# FT2232H.net
KiCad netlist of a schematic drawn in Altium Designer
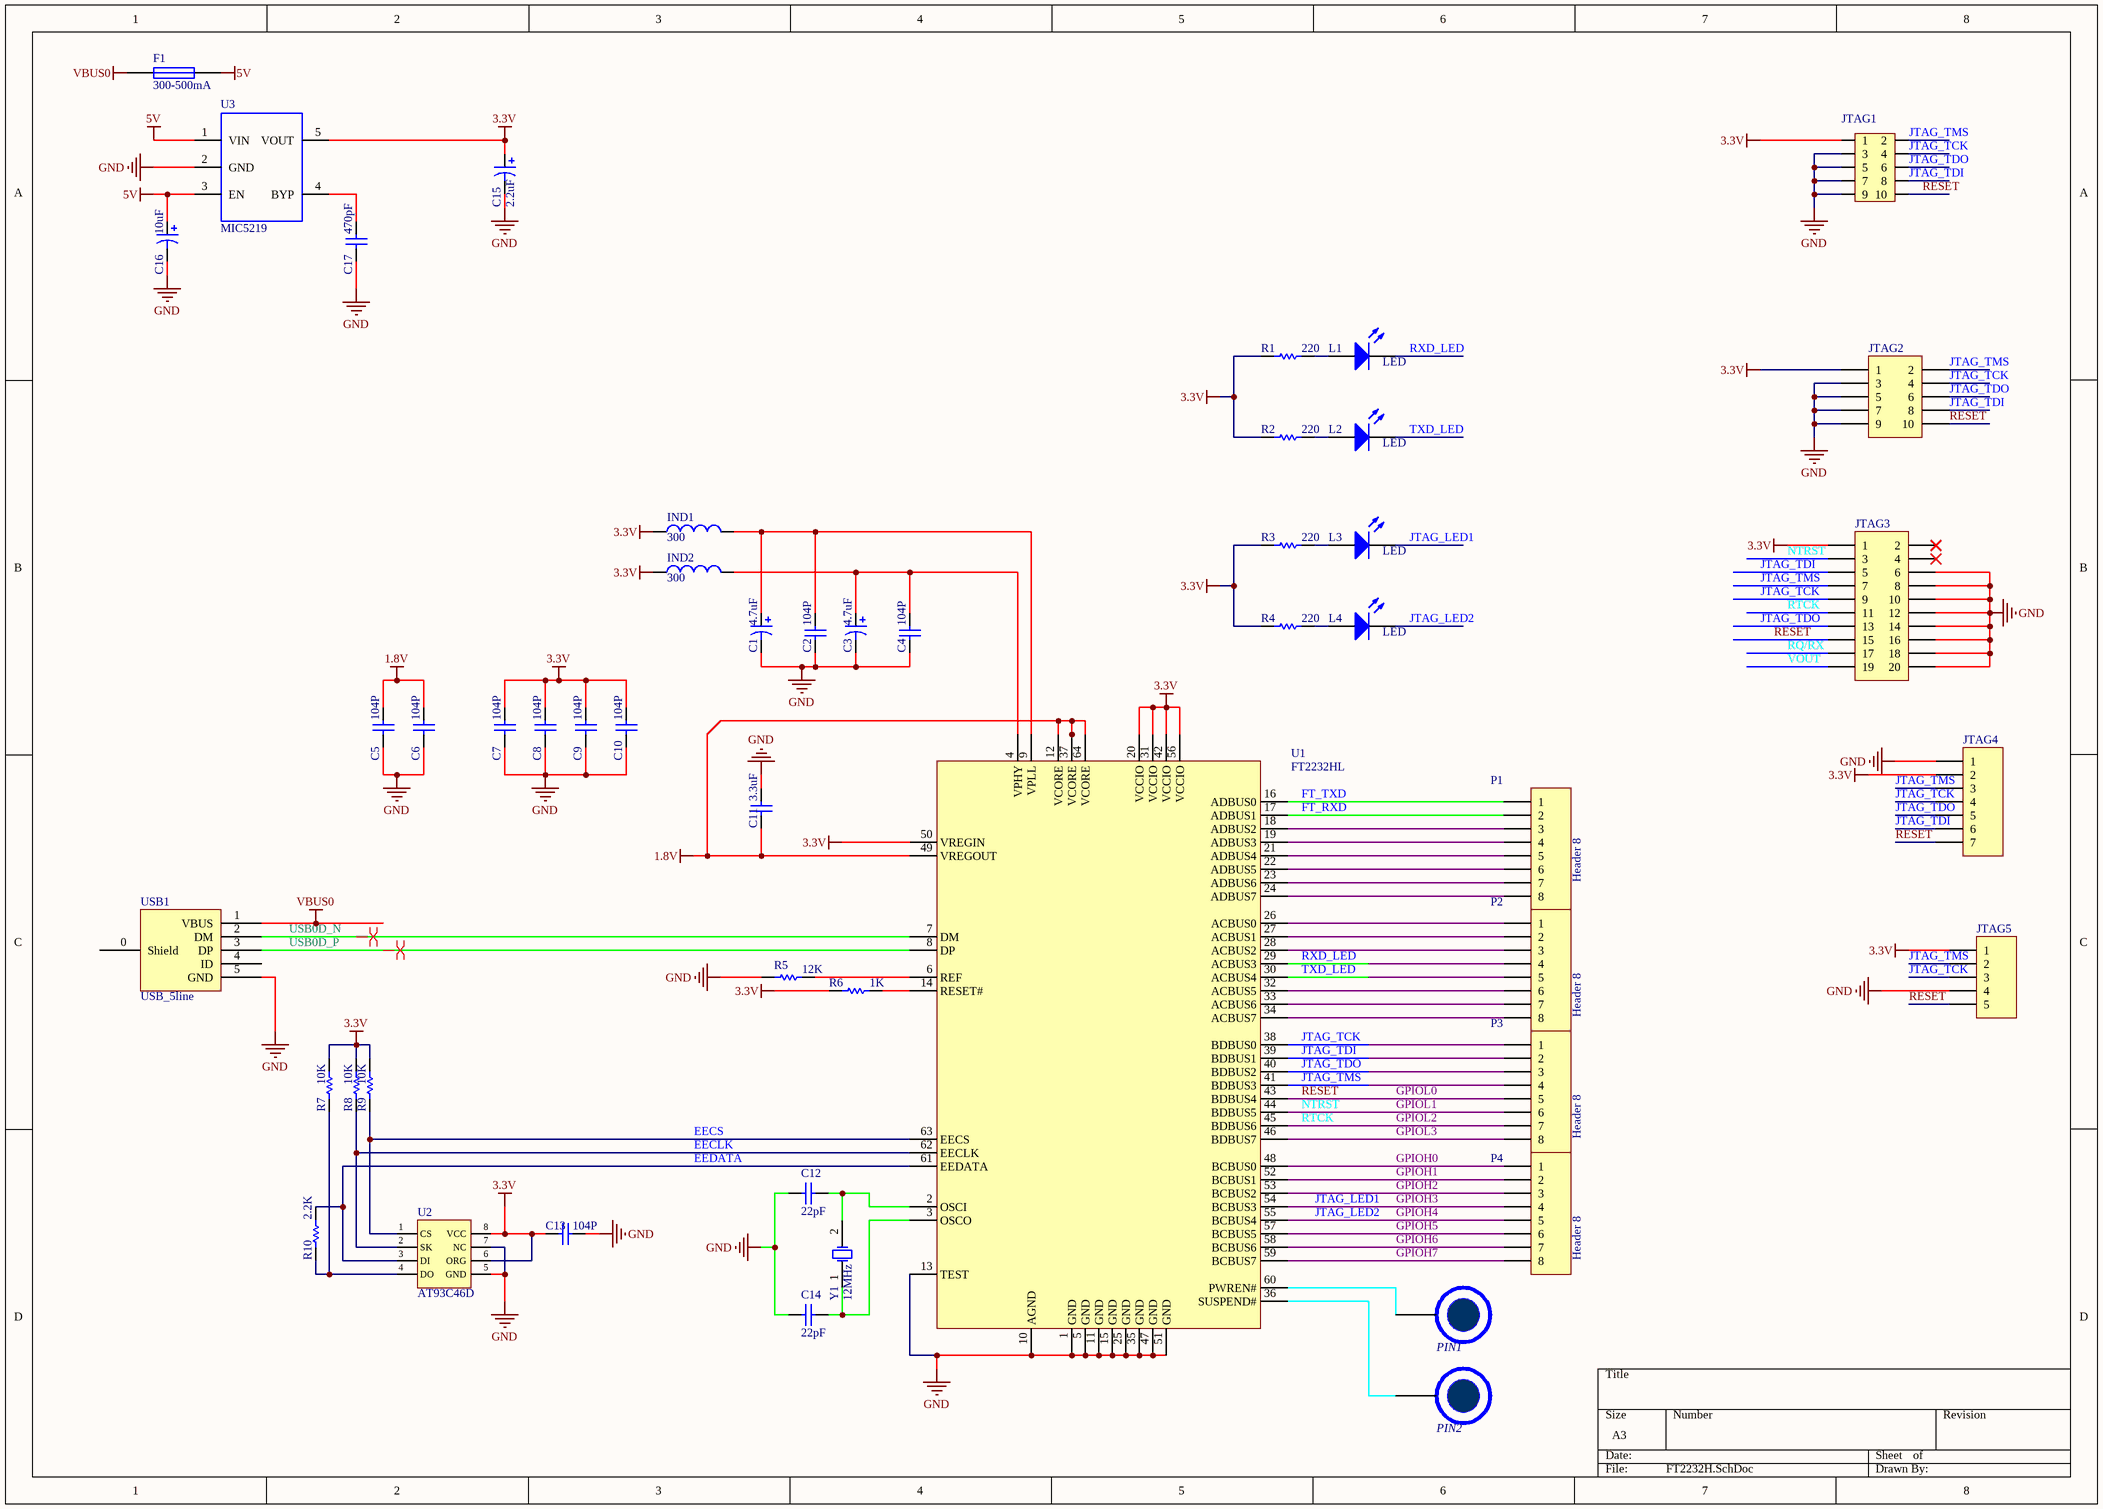
[diagram p0: FT2232H.SchDoc]

(export (version "E")
  (design (tool "Eeschema 10.0.6"))
  (components
    (comp (ref "C1")
      (value "4.7uF")
      (footprint "1608[0603]")
      (description "Polarized Capacitor (Radial)")
      (fields (field (name "Comment") "Cap Pol1") (field (name "PUBLISHER") "Altium Limited"))
      (libsource (lib "Miscellaneous Devices") (part "Cap Pol1"))
    )
    (comp (ref "C2")
      (value "104P")
      (footprint "1608[0603]")
      (description "贴片电容")
      (fields (field (name "Comment") "Cap") (field (name "PUBLISHER") "Altium Limited"))
      (libsource (lib "Sparks") (part "Cap"))
    )
    (comp (ref "C3")
      (value "4.7uF")
      (footprint "1608[0603]")
      (description "Polarized Capacitor (Radial)")
      (fields (field (name "Comment") "Cap Pol1") (field (name "PUBLISHER") "Altium Limited"))
      (libsource (lib "Miscellaneous Devices") (part "Cap Pol1"))
    )
    (comp (ref "C4")
      (value "104P")
      (footprint "1608[0603]")
      (description "贴片电容")
      (fields (field (name "Comment") "Cap") (field (name "PUBLISHER") "Altium Limited"))
      (libsource (lib "Sparks") (part "Cap"))
    )
    (comp (ref "C5")
      (value "104P")
      (footprint "1608[0603]")
      (description "贴片电容")
      (fields (field (name "Comment") "Cap") (field (name "PUBLISHER") "Altium Limited"))
      (libsource (lib "Sparks") (part "Cap"))
    )
    (comp (ref "C6")
      (value "104P")
      (footprint "1608[0603]")
      (description "贴片电容")
      (fields (field (name "Comment") "Cap") (field (name "PUBLISHER") "Altium Limited"))
      (libsource (lib "Sparks") (part "Cap"))
    )
    (comp (ref "C7")
      (value "104P")
      (footprint "1608[0603]")
      (description "贴片电容")
      (fields (field (name "Comment") "Cap") (field (name "PUBLISHER") "Altium Limited"))
      (libsource (lib "Sparks") (part "Cap"))
    )
    (comp (ref "C8")
      (value "104P")
      (footprint "1608[0603]")
      (description "贴片电容")
      (fields (field (name "Comment") "Cap") (field (name "PUBLISHER") "Altium Limited"))
      (libsource (lib "Sparks") (part "Cap"))
    )
    (comp (ref "C9")
      (value "104P")
      (footprint "1608[0603]")
      (description "贴片电容")
      (fields (field (name "Comment") "Cap") (field (name "PUBLISHER") "Altium Limited"))
      (libsource (lib "Sparks") (part "Cap"))
    )
    (comp (ref "C10")
      (value "104P")
      (footprint "1608[0603]")
      (description "贴片电容")
      (fields (field (name "Comment") "Cap") (field (name "PUBLISHER") "Altium Limited"))
      (libsource (lib "Sparks") (part "Cap"))
    )
    (comp (ref "C11")
      (value "3.3uF")
      (footprint "1608[0603]")
      (description "贴片电容")
      (fields (field (name "Comment") "Cap") (field (name "PUBLISHER") "Altium Limited"))
      (libsource (lib "Sparks") (part "Cap"))
    )
    (comp (ref "C12")
      (value "22pF")
      (footprint "1608[0603]")
      (description "贴片电容")
      (fields (field (name "Comment") "Cap") (field (name "PUBLISHER") "Altium Limited"))
      (libsource (lib "Sparks") (part "Cap"))
    )
    (comp (ref "C13")
      (value "104P")
      (footprint "1608[0603]")
      (description "贴片电容")
      (fields (field (name "Comment") "Cap") (field (name "PUBLISHER") "Altium Limited"))
      (libsource (lib "Sparks") (part "Cap"))
    )
    (comp (ref "C14")
      (value "22pF")
      (footprint "1608[0603]")
      (description "贴片电容")
      (fields (field (name "Comment") "Cap") (field (name "PUBLISHER") "Altium Limited"))
      (libsource (lib "Sparks") (part "Cap"))
    )
    (comp (ref "C15")
      (value "2.2uF")
      (footprint "1206(2)")
      (description "Polarized Capacitor (Radial)")
      (fields (field (name "Comment") "Cap Pol1") (field (name "PUBLISHER") "Altium Limited"))
      (libsource (lib "Miscellaneous Devices") (part "Cap Pol1"))
    )
    (comp (ref "C16")
      (value "10uF")
      (footprint "1206(2)")
      (description "Polarized Capacitor (Radial)")
      (fields (field (name "Comment") "Cap Pol1") (field (name "PUBLISHER") "Altium Limited"))
      (libsource (lib "Miscellaneous Devices") (part "Cap Pol1"))
    )
    (comp (ref "C17")
      (value "470pF")
      (footprint "1608[0603]")
      (description "贴片电容")
      (fields (field (name "Comment") "Cap") (field (name "PUBLISHER") "Altium Limited"))
      (libsource (lib "Sparks") (part "Cap"))
    )
    (comp (ref "F1")
      (value "300-500mA")
      (footprint "1206(2)")
      (description "Fuse")
      (fields (field (name "PUBLISHER") "Altium Limited"))
      (libsource (lib "K60-V4.0") (part "Fuse 1"))
    )
    (comp (ref "IND1")
      (value "300")
      (footprint "1608[0603]")
      (description "Inductor")
      (fields (field (name "PUBLISHER") "Altium Limited"))
      (libsource (lib "Miscellaneous Devices") (part "Inductor"))
    )
    (comp (ref "IND2")
      (value "300")
      (footprint "1608[0603]")
      (description "Inductor")
      (fields (field (name "PUBLISHER") "Altium Limited"))
      (libsource (lib "Miscellaneous Devices") (part "Inductor"))
    )
    (comp (ref "JTAG1")
      (value "Header 5X2")
      (footprint "IDC5X2")
      (description "Header, 5-Pin, Dual row")
      (libsource (lib "K60-V4.0") (part "Header 5X2"))
    )
    (comp (ref "JTAG2")
      (value "MHDR2X5")
      (footprint "MHDR2X5")
      (description "Header, 5-Pin, Dual row")
      (fields (field (name "PUBLISHER") "Altium Limited"))
      (libsource (lib "Miscellaneous Connectors") (part "MHDR2X5"))
    )
    (comp (ref "JTAG3")
      (value "Header 10X2")
      (footprint "HDR2X10")
      (description "Header, 10-Pin, Dual row")
      (fields (field (name "PUBLISHER") "Altium Limited"))
      (libsource (lib "Sparks") (part "Header 10X2"))
    )
    (comp (ref "JTAG4")
      (value "MHDR1X7")
      (footprint "MHDR1X7")
      (description "Header, 7-Pin")
      (fields (field (name "PUBLISHER") "Altium Limited"))
      (libsource (lib "Miscellaneous Connectors") (part "MHDR1X7"))
    )
    (comp (ref "JTAG5")
      (value "Header 5")
      (footprint "HDR1X5")
      (description "Header, 5-Pin")
      (fields (field (name "PUBLISHER") "Altium Limited"))
      (libsource (lib "Miscellaneous Connectors") (part "Header 5"))
    )
    (comp (ref "L1") (value "LED") (footprint "1608[0603]") (libsource (lib "Sparks") (part "LED")))
    (comp (ref "L2") (value "LED") (footprint "1608[0603]") (libsource (lib "Sparks") (part "LED")))
    (comp (ref "L3") (value "LED") (footprint "1608[0603]") (libsource (lib "Sparks") (part "LED")))
    (comp (ref "L4") (value "LED") (footprint "1608[0603]") (libsource (lib "Sparks") (part "LED")))
    (comp (ref "P1")
      (value "Header 8")
      (footprint "HDR1X8")
      (description "Header, 8-Pin")
      (fields (field (name "PUBLISHER") "Altium Limited"))
      (libsource (lib "Sparks") (part "Header 8"))
    )
    (comp (ref "P2")
      (value "Header 8")
      (footprint "HDR1X8")
      (description "Header, 8-Pin")
      (fields (field (name "PUBLISHER") "Altium Limited"))
      (libsource (lib "Sparks") (part "Header 8"))
    )
    (comp (ref "P3")
      (value "Header 8")
      (footprint "HDR1X8")
      (description "Header, 8-Pin")
      (fields (field (name "PUBLISHER") "Altium Limited"))
      (libsource (lib "Sparks") (part "Header 8"))
    )
    (comp (ref "P4")
      (value "Header 8")
      (footprint "HDR1X8")
      (description "Header, 8-Pin")
      (fields (field (name "PUBLISHER") "Altium Limited"))
      (libsource (lib "Sparks") (part "Header 8"))
    )
    (comp (ref "PIN1") (value "PIN") (footprint "PIN") (libsource (lib "2号库") (part "PIN")))
    (comp (ref "PIN2") (value "PIN") (footprint "PIN") (libsource (lib "2号库") (part "PIN")))
    (comp (ref "R1")
      (value "220")
      (footprint "1608[0603]")
      (description "贴片电阻")
      (fields (field (name "Comment") "Res") (field (name "PUBLISHER") "Altium Limited"))
      (libsource (lib "Sparks") (part "Res"))
    )
    (comp (ref "R2")
      (value "220")
      (footprint "1608[0603]")
      (description "贴片电阻")
      (fields (field (name "Comment") "Res") (field (name "PUBLISHER") "Altium Limited"))
      (libsource (lib "Sparks") (part "Res"))
    )
    (comp (ref "R3")
      (value "220")
      (footprint "1608[0603]")
      (description "贴片电阻")
      (fields (field (name "Comment") "Res") (field (name "PUBLISHER") "Altium Limited"))
      (libsource (lib "Sparks") (part "Res"))
    )
    (comp (ref "R4")
      (value "220")
      (footprint "1608[0603]")
      (description "贴片电阻")
      (fields (field (name "Comment") "Res") (field (name "PUBLISHER") "Altium Limited"))
      (libsource (lib "Sparks") (part "Res"))
    )
    (comp (ref "R5")
      (value "12K")
      (footprint "1608[0603]")
      (description "贴片电阻")
      (fields (field (name "Comment") "Res") (field (name "PUBLISHER") "Altium Limited"))
      (libsource (lib "Sparks") (part "Res"))
    )
    (comp (ref "R6")
      (value "1K")
      (footprint "1608[0603]")
      (description "贴片电阻")
      (fields (field (name "Comment") "Res") (field (name "PUBLISHER") "Altium Limited"))
      (libsource (lib "Sparks") (part "Res"))
    )
    (comp (ref "R7")
      (value "10K")
      (footprint "1608[0603]")
      (description "贴片电阻")
      (fields (field (name "Comment") "Res") (field (name "PUBLISHER") "Altium Limited"))
      (libsource (lib "Sparks") (part "Res"))
    )
    (comp (ref "R8")
      (value "10K")
      (footprint "1608[0603]")
      (description "贴片电阻")
      (fields (field (name "Comment") "Res") (field (name "PUBLISHER") "Altium Limited"))
      (libsource (lib "Sparks") (part "Res"))
    )
    (comp (ref "R9")
      (value "10K")
      (footprint "1608[0603]")
      (description "贴片电阻")
      (fields (field (name "Comment") "Res") (field (name "PUBLISHER") "Altium Limited"))
      (libsource (lib "Sparks") (part "Res"))
    )
    (comp (ref "R10")
      (value "2.2K")
      (footprint "1608[0603]")
      (description "贴片电阻")
      (fields (field (name "Comment") "Res") (field (name "PUBLISHER") "Altium Limited"))
      (libsource (lib "Sparks") (part "Res"))
    )
    (comp (ref "U1") (value "FT2232HL") (footprint "LQFP-64") (libsource (lib "2号库") (part "FT2232HL")))
    (comp (ref "U2")
      (value "AT93C46D")
      (footprint "TSOP65P640X120-8N-AT93C46D")
      (libsource (lib "2号库") (part "AT93C46D"))
    )
    (comp (ref "U3")
      (value "MIC5219")
      (footprint "SOT-23-5")
      (description "LDO")
      (libsource (lib "K60-V4.0") (part "MIC5219"))
    )
    (comp (ref "USB1")
      (value "USB_5line")
      (footprint "USB-MICRO-5P-2F")
      (libsource (lib "2号库") (part "USB_5line"))
    )
    (comp (ref "Y1")
      (value "12MHz")
      (footprint "5032")
      (description "晶体振荡器")
      (fields (field (name "PUBLISHER") "Altium Limited"))
      (libsource (lib "Sparks") (part "XTAL"))
    )
  )
  (nets
    (net (code "1") (name "/EECLK") (class "Default")
      (node (ref "R8") (pin "2") (pinfunction "2_2") (pintype "passive"))
      (node (ref "U1") (pin "62") (pinfunction "EECLK_62") (pintype "passive"))
      (node (ref "U2") (pin "2") (pinfunction "SK_2") (pintype "passive"))
    )
    (net (code "2") (name "/EECS") (class "Default")
      (node (ref "R9") (pin "2") (pinfunction "2_2") (pintype "passive"))
      (node (ref "U1") (pin "63") (pinfunction "EECS_63") (pintype "passive"))
      (node (ref "U2") (pin "1") (pinfunction "CS_1") (pintype "passive"))
    )
    (net (code "3") (name "/EEDATA") (class "Default")
      (node (ref "R10") (pin "1") (pinfunction "1_1") (pintype "passive"))
      (node (ref "U1") (pin "61") (pinfunction "EEDATA_61") (pintype "passive"))
      (node (ref "U2") (pin "3") (pinfunction "DI_3") (pintype "passive"))
    )
    (net (code "4") (name "/FT_RXD") (class "Default")
      (node (ref "P1") (pin "2") (pinfunction "2_2") (pintype "passive"))
      (node (ref "U1") (pin "17") (pinfunction "ADBUS1_17") (pintype "passive"))
    )
    (net (code "5") (name "/FT_TXD") (class "Default")
      (node (ref "P1") (pin "1") (pinfunction "1_1") (pintype "passive"))
      (node (ref "U1") (pin "16") (pinfunction "ADBUS0_16") (pintype "passive"))
    )
    (net (code "6") (name "/GPIOH0") (class "Default")
      (node (ref "P4") (pin "1") (pinfunction "1_1") (pintype "passive"))
      (node (ref "U1") (pin "48") (pinfunction "BCBUS0_48") (pintype "passive"))
    )
    (net (code "7") (name "/GPIOH1") (class "Default")
      (node (ref "P4") (pin "2") (pinfunction "2_2") (pintype "passive"))
      (node (ref "U1") (pin "52") (pinfunction "BCBUS1_52") (pintype "passive"))
    )
    (net (code "8") (name "/GPIOH2") (class "Default")
      (node (ref "P4") (pin "3") (pinfunction "3_3") (pintype "passive"))
      (node (ref "U1") (pin "53") (pinfunction "BCBUS2_53") (pintype "passive"))
    )
    (net (code "9") (name "/GPIOH3") (class "Default")
      (node (ref "L3") (pin "2") (pinfunction "K_2") (pintype "passive"))
      (node (ref "P4") (pin "4") (pinfunction "4_4") (pintype "passive"))
      (node (ref "U1") (pin "54") (pinfunction "BCBUS3_54") (pintype "passive"))
    )
    (net (code "10") (name "/GPIOH4") (class "Default")
      (node (ref "L4") (pin "2") (pinfunction "K_2") (pintype "passive"))
      (node (ref "P4") (pin "5") (pinfunction "5_5") (pintype "passive"))
      (node (ref "U1") (pin "55") (pinfunction "BCBUS4_55") (pintype "passive"))
    )
    (net (code "11") (name "/GPIOH5") (class "Default")
      (node (ref "P4") (pin "6") (pinfunction "6_6") (pintype "passive"))
      (node (ref "U1") (pin "57") (pinfunction "BCBUS5_57") (pintype "passive"))
    )
    (net (code "12") (name "/GPIOH6") (class "Default")
      (node (ref "P4") (pin "7") (pinfunction "7_7") (pintype "passive"))
      (node (ref "U1") (pin "58") (pinfunction "BCBUS6_58") (pintype "passive"))
    )
    (net (code "13") (name "/GPIOH7") (class "Default")
      (node (ref "P4") (pin "8") (pinfunction "8_8") (pintype "passive"))
      (node (ref "U1") (pin "59") (pinfunction "BCBUS7_59") (pintype "passive"))
    )
    (net (code "14") (name "/GPIOL0") (class "Default")
      (node (ref "JTAG1") (pin "10") (pinfunction "10_10") (pintype "passive"))
      (node (ref "JTAG2") (pin "10") (pinfunction "10_10") (pintype "passive"))
      (node (ref "JTAG3") (pin "15") (pinfunction "15_15") (pintype "passive"))
      (node (ref "JTAG4") (pin "7") (pinfunction "7_7") (pintype "passive"))
      (node (ref "JTAG5") (pin "5") (pinfunction "5_5") (pintype "passive"))
      (node (ref "P3") (pin "5") (pinfunction "5_5") (pintype "passive"))
      (node (ref "U1") (pin "43") (pinfunction "BDBUS4_43") (pintype "passive"))
    )
    (net (code "15") (name "/GPIOL1") (class "Default")
      (node (ref "JTAG3") (pin "3") (pinfunction "3_3") (pintype "passive"))
      (node (ref "P3") (pin "6") (pinfunction "6_6") (pintype "passive"))
      (node (ref "U1") (pin "44") (pinfunction "BDBUS5_44") (pintype "passive"))
    )
    (net (code "16") (name "/GPIOL2") (class "Default")
      (node (ref "JTAG3") (pin "11") (pinfunction "11_11") (pintype "passive"))
      (node (ref "P3") (pin "7") (pinfunction "7_7") (pintype "passive"))
      (node (ref "U1") (pin "45") (pinfunction "BDBUS6_45") (pintype "passive"))
    )
    (net (code "17") (name "/GPIOL3") (class "Default")
      (node (ref "P3") (pin "8") (pinfunction "8_8") (pintype "passive"))
      (node (ref "U1") (pin "46") (pinfunction "BDBUS7_46") (pintype "passive"))
    )
    (net (code "18") (name "/JTAG_TCK") (class "Default")
      (node (ref "JTAG1") (pin "4") (pinfunction "4_4") (pintype "passive"))
      (node (ref "JTAG2") (pin "4") (pinfunction "4_4") (pintype "passive"))
      (node (ref "JTAG3") (pin "9") (pinfunction "9_9") (pintype "passive"))
      (node (ref "JTAG4") (pin "4") (pinfunction "4_4") (pintype "passive"))
      (node (ref "JTAG5") (pin "3") (pinfunction "3_3") (pintype "passive"))
      (node (ref "P3") (pin "1") (pinfunction "1_1") (pintype "passive"))
      (node (ref "U1") (pin "38") (pinfunction "BDBUS0_38") (pintype "passive"))
    )
    (net (code "19") (name "/JTAG_TDI") (class "Default")
      (node (ref "JTAG1") (pin "8") (pinfunction "8_8") (pintype "passive"))
      (node (ref "JTAG2") (pin "8") (pinfunction "8_8") (pintype "passive"))
      (node (ref "JTAG3") (pin "5") (pinfunction "5_5") (pintype "passive"))
      (node (ref "JTAG4") (pin "6") (pinfunction "6_6") (pintype "passive"))
      (node (ref "P3") (pin "2") (pinfunction "2_2") (pintype "passive"))
      (node (ref "U1") (pin "39") (pinfunction "BDBUS1_39") (pintype "passive"))
    )
    (net (code "20") (name "/JTAG_TDO") (class "Default")
      (node (ref "JTAG1") (pin "6") (pinfunction "6_6") (pintype "passive"))
      (node (ref "JTAG2") (pin "6") (pinfunction "6_6") (pintype "passive"))
      (node (ref "JTAG3") (pin "13") (pinfunction "13_13") (pintype "passive"))
      (node (ref "JTAG4") (pin "5") (pinfunction "5_5") (pintype "passive"))
      (node (ref "P3") (pin "3") (pinfunction "3_3") (pintype "passive"))
      (node (ref "U1") (pin "40") (pinfunction "BDBUS2_40") (pintype "passive"))
    )
    (net (code "21") (name "/JTAG_TMS") (class "Default")
      (node (ref "JTAG1") (pin "2") (pinfunction "2_2") (pintype "passive"))
      (node (ref "JTAG2") (pin "2") (pinfunction "2_2") (pintype "passive"))
      (node (ref "JTAG3") (pin "7") (pinfunction "7_7") (pintype "passive"))
      (node (ref "JTAG4") (pin "3") (pinfunction "3_3") (pintype "passive"))
      (node (ref "JTAG5") (pin "2") (pinfunction "2_2") (pintype "passive"))
      (node (ref "P3") (pin "4") (pinfunction "4_4") (pintype "passive"))
      (node (ref "U1") (pin "41") (pinfunction "BDBUS3_41") (pintype "passive"))
    )
    (net (code "22") (name "/RQ{slash}RX") (class "Default")
      (node (ref "JTAG3") (pin "17") (pinfunction "17_17") (pintype "passive"))
    )
    (net (code "23") (name "/RXD_LED") (class "Default")
      (node (ref "L1") (pin "2") (pinfunction "K_2") (pintype "passive"))
      (node (ref "P2") (pin "4") (pinfunction "4_4") (pintype "passive"))
      (node (ref "U1") (pin "29") (pinfunction "ACBUS3_29") (pintype "passive"))
    )
    (net (code "24") (name "/TXD_LED") (class "Default")
      (node (ref "L2") (pin "2") (pinfunction "K_2") (pintype "passive"))
      (node (ref "P2") (pin "5") (pinfunction "5_5") (pintype "passive"))
      (node (ref "U1") (pin "30") (pinfunction "ACBUS4_30") (pintype "passive"))
    )
    (net (code "25") (name "/USB0D_N") (class "Default")
      (node (ref "U1") (pin "7") (pinfunction "DM_7") (pintype "passive"))
      (node (ref "USB1") (pin "2") (pinfunction "DM_2") (pintype "passive"))
    )
    (net (code "26") (name "/USB0D_P") (class "Default")
      (node (ref "U1") (pin "8") (pinfunction "DP_8") (pintype "passive"))
      (node (ref "USB1") (pin "3") (pinfunction "DP_3") (pintype "passive"))
    )
    (net (code "27") (name "/VOUT") (class "Default")
      (node (ref "JTAG3") (pin "19") (pinfunction "19_19") (pintype "passive"))
    )
    (net (code "28") (name "1.8V") (class "Default")
      (node (ref "C11") (pin "1") (pinfunction "1_1") (pintype "passive"))
      (node (ref "C5") (pin "2") (pinfunction "2_2") (pintype "passive"))
      (node (ref "C6") (pin "2") (pinfunction "2_2") (pintype "passive"))
      (node (ref "U1") (pin "12") (pinfunction "VCORE_12") (pintype "passive"))
      (node (ref "U1") (pin "37") (pinfunction "VCORE_37") (pintype "passive"))
      (node (ref "U1") (pin "49") (pinfunction "VREGOUT_49") (pintype "passive"))
      (node (ref "U1") (pin "64") (pinfunction "VCORE_64") (pintype "passive"))
    )
    (net (code "29") (name "3.3V") (class "Default")
      (node (ref "C10") (pin "2") (pinfunction "2_2") (pintype "passive"))
      (node (ref "C13") (pin "2") (pinfunction "2_2") (pintype "passive"))
      (node (ref "C15") (pin "1") (pinfunction "1_1") (pintype "passive"))
      (node (ref "C7") (pin "2") (pinfunction "2_2") (pintype "passive"))
      (node (ref "C8") (pin "2") (pinfunction "2_2") (pintype "passive"))
      (node (ref "C9") (pin "2") (pinfunction "2_2") (pintype "passive"))
      (node (ref "IND1") (pin "1") (pinfunction "1_1") (pintype "passive"))
      (node (ref "IND2") (pin "1") (pinfunction "1_1") (pintype "passive"))
      (node (ref "JTAG1") (pin "1") (pinfunction "1_1") (pintype "passive"))
      (node (ref "JTAG2") (pin "1") (pinfunction "1_1") (pintype "passive"))
      (node (ref "JTAG3") (pin "1") (pinfunction "1_1") (pintype "passive"))
      (node (ref "JTAG4") (pin "2") (pinfunction "2_2") (pintype "passive"))
      (node (ref "JTAG5") (pin "1") (pinfunction "1_1") (pintype "passive"))
      (node (ref "R1") (pin "2") (pinfunction "2_2") (pintype "passive"))
      (node (ref "R2") (pin "2") (pinfunction "2_2") (pintype "passive"))
      (node (ref "R3") (pin "2") (pinfunction "2_2") (pintype "passive"))
      (node (ref "R4") (pin "2") (pinfunction "2_2") (pintype "passive"))
      (node (ref "R6") (pin "2") (pinfunction "2_2") (pintype "passive"))
      (node (ref "R7") (pin "1") (pinfunction "1_1") (pintype "passive"))
      (node (ref "R8") (pin "1") (pinfunction "1_1") (pintype "passive"))
      (node (ref "R9") (pin "1") (pinfunction "1_1") (pintype "passive"))
      (node (ref "U1") (pin "20") (pinfunction "VCCIO_20") (pintype "passive"))
      (node (ref "U1") (pin "31") (pinfunction "VCCIO_31") (pintype "passive"))
      (node (ref "U1") (pin "42") (pinfunction "VCCIO_42") (pintype "passive"))
      (node (ref "U1") (pin "50") (pinfunction "VREGIN_50") (pintype "passive"))
      (node (ref "U1") (pin "56") (pinfunction "VCCIO_56") (pintype "passive"))
      (node (ref "U2") (pin "6") (pinfunction "ORG_6") (pintype "passive"))
      (node (ref "U2") (pin "8") (pinfunction "VCC_8") (pintype "passive"))
      (node (ref "U3") (pin "5") (pinfunction "VOUT_5") (pintype "passive"))
    )
    (net (code "30") (name "5V") (class "Default")
      (node (ref "C16") (pin "1") (pinfunction "1_1") (pintype "passive"))
      (node (ref "F1") (pin "2") (pinfunction "2_2") (pintype "passive"))
      (node (ref "U3") (pin "1") (pinfunction "VIN_1") (pintype "passive"))
      (node (ref "U3") (pin "3") (pinfunction "EN_3") (pintype "passive"))
    )
    (net (code "31") (name "GND") (class "Default")
      (node (ref "C1") (pin "2") (pinfunction "2_2") (pintype "passive"))
      (node (ref "C10") (pin "1") (pinfunction "1_1") (pintype "passive"))
      (node (ref "C11") (pin "2") (pinfunction "2_2") (pintype "passive"))
      (node (ref "C12") (pin "1") (pinfunction "1_1") (pintype "passive"))
      (node (ref "C13") (pin "1") (pinfunction "1_1") (pintype "passive"))
      (node (ref "C14") (pin "2") (pinfunction "2_2") (pintype "passive"))
      (node (ref "C15") (pin "2") (pinfunction "2_2") (pintype "passive"))
      (node (ref "C16") (pin "2") (pinfunction "2_2") (pintype "passive"))
      (node (ref "C17") (pin "1") (pinfunction "1_1") (pintype "passive"))
      (node (ref "C2") (pin "1") (pinfunction "1_1") (pintype "passive"))
      (node (ref "C3") (pin "2") (pinfunction "2_2") (pintype "passive"))
      (node (ref "C4") (pin "1") (pinfunction "1_1") (pintype "passive"))
      (node (ref "C5") (pin "1") (pinfunction "1_1") (pintype "passive"))
      (node (ref "C6") (pin "1") (pinfunction "1_1") (pintype "passive"))
      (node (ref "C7") (pin "1") (pinfunction "1_1") (pintype "passive"))
      (node (ref "C8") (pin "1") (pinfunction "1_1") (pintype "passive"))
      (node (ref "C9") (pin "1") (pinfunction "1_1") (pintype "passive"))
      (node (ref "JTAG1") (pin "3") (pinfunction "3_3") (pintype "passive"))
      (node (ref "JTAG1") (pin "5") (pinfunction "5_5") (pintype "passive"))
      (node (ref "JTAG1") (pin "7") (pinfunction "7_7") (pintype "passive"))
      (node (ref "JTAG1") (pin "9") (pinfunction "9_9") (pintype "passive"))
      (node (ref "JTAG2") (pin "3") (pinfunction "3_3") (pintype "passive"))
      (node (ref "JTAG2") (pin "5") (pinfunction "5_5") (pintype "passive"))
      (node (ref "JTAG2") (pin "7") (pinfunction "7_7") (pintype "passive"))
      (node (ref "JTAG2") (pin "9") (pinfunction "9_9") (pintype "passive"))
      (node (ref "JTAG3") (pin "10") (pinfunction "10_10") (pintype "passive"))
      (node (ref "JTAG3") (pin "12") (pinfunction "12_12") (pintype "passive"))
      (node (ref "JTAG3") (pin "14") (pinfunction "14_14") (pintype "passive"))
      (node (ref "JTAG3") (pin "16") (pinfunction "16_16") (pintype "passive"))
      (node (ref "JTAG3") (pin "18") (pinfunction "18_18") (pintype "passive"))
      (node (ref "JTAG3") (pin "20") (pinfunction "20_20") (pintype "passive"))
      (node (ref "JTAG3") (pin "6") (pinfunction "6_6") (pintype "passive"))
      (node (ref "JTAG3") (pin "8") (pinfunction "8_8") (pintype "passive"))
      (node (ref "JTAG4") (pin "1") (pinfunction "1_1") (pintype "passive"))
      (node (ref "JTAG5") (pin "4") (pinfunction "4_4") (pintype "passive"))
      (node (ref "R5") (pin "2") (pinfunction "2_2") (pintype "passive"))
      (node (ref "U1") (pin "1") (pinfunction "GND_1") (pintype "passive"))
      (node (ref "U1") (pin "10") (pinfunction "AGND_10") (pintype "passive"))
      (node (ref "U1") (pin "11") (pinfunction "GND_11") (pintype "passive"))
      (node (ref "U1") (pin "13") (pinfunction "TEST_13") (pintype "passive"))
      (node (ref "U1") (pin "15") (pinfunction "GND_15") (pintype "passive"))
      (node (ref "U1") (pin "25") (pinfunction "GND_25") (pintype "passive"))
      (node (ref "U1") (pin "35") (pinfunction "GND_35") (pintype "passive"))
      (node (ref "U1") (pin "47") (pinfunction "GND_47") (pintype "passive"))
      (node (ref "U1") (pin "5") (pinfunction "GND_5") (pintype "passive"))
      (node (ref "U1") (pin "51") (pinfunction "GND_51") (pintype "passive"))
      (node (ref "U2") (pin "5") (pinfunction "GND_5") (pintype "passive"))
      (node (ref "U2") (pin "7") (pinfunction "NC_7") (pintype "passive"))
      (node (ref "U3") (pin "2") (pinfunction "GND_2") (pintype "passive"))
      (node (ref "USB1") (pin "5") (pinfunction "GND_5") (pintype "passive"))
    )
    (net (code "32") (name "Net-(L1-A)") (class "Default")
      (node (ref "L1") (pin "1") (pinfunction "A_1") (pintype "passive"))
      (node (ref "R1") (pin "1") (pinfunction "1_1") (pintype "passive"))
    )
    (net (code "33") (name "Net-(L2-A)") (class "Default")
      (node (ref "L2") (pin "1") (pinfunction "A_1") (pintype "passive"))
      (node (ref "R2") (pin "1") (pinfunction "1_1") (pintype "passive"))
    )
    (net (code "34") (name "Net-(L3-A)") (class "Default")
      (node (ref "L3") (pin "1") (pinfunction "A_1") (pintype "passive"))
      (node (ref "R3") (pin "1") (pinfunction "1_1") (pintype "passive"))
    )
    (net (code "35") (name "Net-(L4-A)") (class "Default")
      (node (ref "L4") (pin "1") (pinfunction "A_1") (pintype "passive"))
      (node (ref "R4") (pin "1") (pinfunction "1_1") (pintype "passive"))
    )
    (net (code "36") (name "Net-(PIN1-PIN)") (class "Default")
      (node (ref "PIN1") (pin "1") (pinfunction "PIN_1") (pintype "passive"))
      (node (ref "U1") (pin "60") (pinfunction "PWREN#_60") (pintype "passive"))
    )
    (net (code "37") (name "Net-(PIN2-PIN)") (class "Default")
      (node (ref "PIN2") (pin "1") (pinfunction "PIN_1") (pintype "passive"))
      (node (ref "U1") (pin "36") (pinfunction "SUSPEND#_36") (pintype "passive"))
    )
    (net (code "38") (name "Net-(U1-ACBUS0)") (class "Default")
      (node (ref "P2") (pin "1") (pinfunction "1_1") (pintype "passive"))
      (node (ref "U1") (pin "26") (pinfunction "ACBUS0_26") (pintype "passive"))
    )
    (net (code "39") (name "Net-(U1-ACBUS1)") (class "Default")
      (node (ref "P2") (pin "2") (pinfunction "2_2") (pintype "passive"))
      (node (ref "U1") (pin "27") (pinfunction "ACBUS1_27") (pintype "passive"))
    )
    (net (code "40") (name "Net-(U1-ACBUS2)") (class "Default")
      (node (ref "P2") (pin "3") (pinfunction "3_3") (pintype "passive"))
      (node (ref "U1") (pin "28") (pinfunction "ACBUS2_28") (pintype "passive"))
    )
    (net (code "41") (name "Net-(U1-ACBUS5)") (class "Default")
      (node (ref "P2") (pin "6") (pinfunction "6_6") (pintype "passive"))
      (node (ref "U1") (pin "32") (pinfunction "ACBUS5_32") (pintype "passive"))
    )
    (net (code "42") (name "Net-(U1-ACBUS6)") (class "Default")
      (node (ref "P2") (pin "7") (pinfunction "7_7") (pintype "passive"))
      (node (ref "U1") (pin "33") (pinfunction "ACBUS6_33") (pintype "passive"))
    )
    (net (code "43") (name "Net-(U1-ACBUS7)") (class "Default")
      (node (ref "P2") (pin "8") (pinfunction "8_8") (pintype "passive"))
      (node (ref "U1") (pin "34") (pinfunction "ACBUS7_34") (pintype "passive"))
    )
    (net (code "44") (name "Net-(U1-ADBUS2)") (class "Default")
      (node (ref "P1") (pin "3") (pinfunction "3_3") (pintype "passive"))
      (node (ref "U1") (pin "18") (pinfunction "ADBUS2_18") (pintype "passive"))
    )
    (net (code "45") (name "Net-(U1-ADBUS3)") (class "Default")
      (node (ref "P1") (pin "4") (pinfunction "4_4") (pintype "passive"))
      (node (ref "U1") (pin "19") (pinfunction "ADBUS3_19") (pintype "passive"))
    )
    (net (code "46") (name "Net-(U1-ADBUS4)") (class "Default")
      (node (ref "P1") (pin "5") (pinfunction "5_5") (pintype "passive"))
      (node (ref "U1") (pin "21") (pinfunction "ADBUS4_21") (pintype "passive"))
    )
    (net (code "47") (name "Net-(U1-ADBUS5)") (class "Default")
      (node (ref "P1") (pin "6") (pinfunction "6_6") (pintype "passive"))
      (node (ref "U1") (pin "22") (pinfunction "ADBUS5_22") (pintype "passive"))
    )
    (net (code "48") (name "Net-(U1-ADBUS6)") (class "Default")
      (node (ref "P1") (pin "7") (pinfunction "7_7") (pintype "passive"))
      (node (ref "U1") (pin "23") (pinfunction "ADBUS6_23") (pintype "passive"))
    )
    (net (code "49") (name "Net-(U1-ADBUS7)") (class "Default")
      (node (ref "P1") (pin "8") (pinfunction "8_8") (pintype "passive"))
      (node (ref "U1") (pin "24") (pinfunction "ADBUS7_24") (pintype "passive"))
    )
    (net (code "50") (name "Net-(U1-OSCI)") (class "Default")
      (node (ref "C12") (pin "2") (pinfunction "2_2") (pintype "passive"))
      (node (ref "U1") (pin "2") (pinfunction "OSCI_2") (pintype "passive"))
      (node (ref "Y1") (pin "2") (pinfunction "OSC2_2") (pintype "passive"))
    )
    (net (code "51") (name "Net-(U1-OSCO)") (class "Default")
      (node (ref "C14") (pin "1") (pinfunction "1_1") (pintype "passive"))
      (node (ref "U1") (pin "3") (pinfunction "OSCO_3") (pintype "passive"))
      (node (ref "Y1") (pin "1") (pinfunction "OSC1_1") (pintype "passive"))
    )
    (net (code "52") (name "Net-(U1-REF)") (class "Default")
      (node (ref "R5") (pin "1") (pinfunction "1_1") (pintype "passive"))
      (node (ref "U1") (pin "6") (pinfunction "REF_6") (pintype "passive"))
    )
    (net (code "53") (name "Net-(U1-RESET#)") (class "Default")
      (node (ref "R6") (pin "1") (pinfunction "1_1") (pintype "passive"))
      (node (ref "U1") (pin "14") (pinfunction "RESET#_14") (pintype "passive"))
    )
    (net (code "54") (name "Net-(U1-VPHY)") (class "Default")
      (node (ref "C3") (pin "1") (pinfunction "1_1") (pintype "passive"))
      (node (ref "C4") (pin "2") (pinfunction "2_2") (pintype "passive"))
      (node (ref "IND2") (pin "2") (pinfunction "2_2") (pintype "passive"))
      (node (ref "U1") (pin "4") (pinfunction "VPHY_4") (pintype "passive"))
    )
    (net (code "55") (name "Net-(U1-VPLL)") (class "Default")
      (node (ref "C1") (pin "1") (pinfunction "1_1") (pintype "passive"))
      (node (ref "C2") (pin "2") (pinfunction "2_2") (pintype "passive"))
      (node (ref "IND1") (pin "2") (pinfunction "2_2") (pintype "passive"))
      (node (ref "U1") (pin "9") (pinfunction "VPLL_9") (pintype "passive"))
    )
    (net (code "56") (name "Net-(U2-DO)") (class "Default")
      (node (ref "R10") (pin "2") (pinfunction "2_2") (pintype "passive"))
      (node (ref "R7") (pin "2") (pinfunction "2_2") (pintype "passive"))
      (node (ref "U2") (pin "4") (pinfunction "DO_4") (pintype "passive"))
    )
    (net (code "57") (name "Net-(U3-BYP)") (class "Default")
      (node (ref "C17") (pin "2") (pinfunction "2_2") (pintype "passive"))
      (node (ref "U3") (pin "4") (pinfunction "BYP_4") (pintype "passive"))
    )
    (net (code "58") (name "VBUS0") (class "Default")
      (node (ref "F1") (pin "1") (pinfunction "1_1") (pintype "passive"))
      (node (ref "USB1") (pin "1") (pinfunction "VBUS_1") (pintype "passive"))
    )
    (net (code "59") (name "unconnected-(JTAG3-Pad2)") (class "Default")
      (node (ref "JTAG3") (pin "2") (pinfunction "2_2") (pintype "passive+no_connect"))
    )
    (net (code "60") (name "unconnected-(JTAG3-Pad4)") (class "Default")
      (node (ref "JTAG3") (pin "4") (pinfunction "4_4") (pintype "passive+no_connect"))
    )
    (net (code "61") (name "unconnected-(USB1-ID-Pad4)") (class "Default")
      (node (ref "USB1") (pin "4") (pinfunction "ID_4") (pintype "passive"))
    )
    (net (code "62") (name "unconnected-(USB1-Shield-Pad0)") (class "Default")
      (node (ref "USB1") (pin "0") (pinfunction "Shield_0") (pintype "passive"))
    )
  )
)
